# Mosfet_Driver.net
KiCad netlist of a schematic drawn in Altium Designer
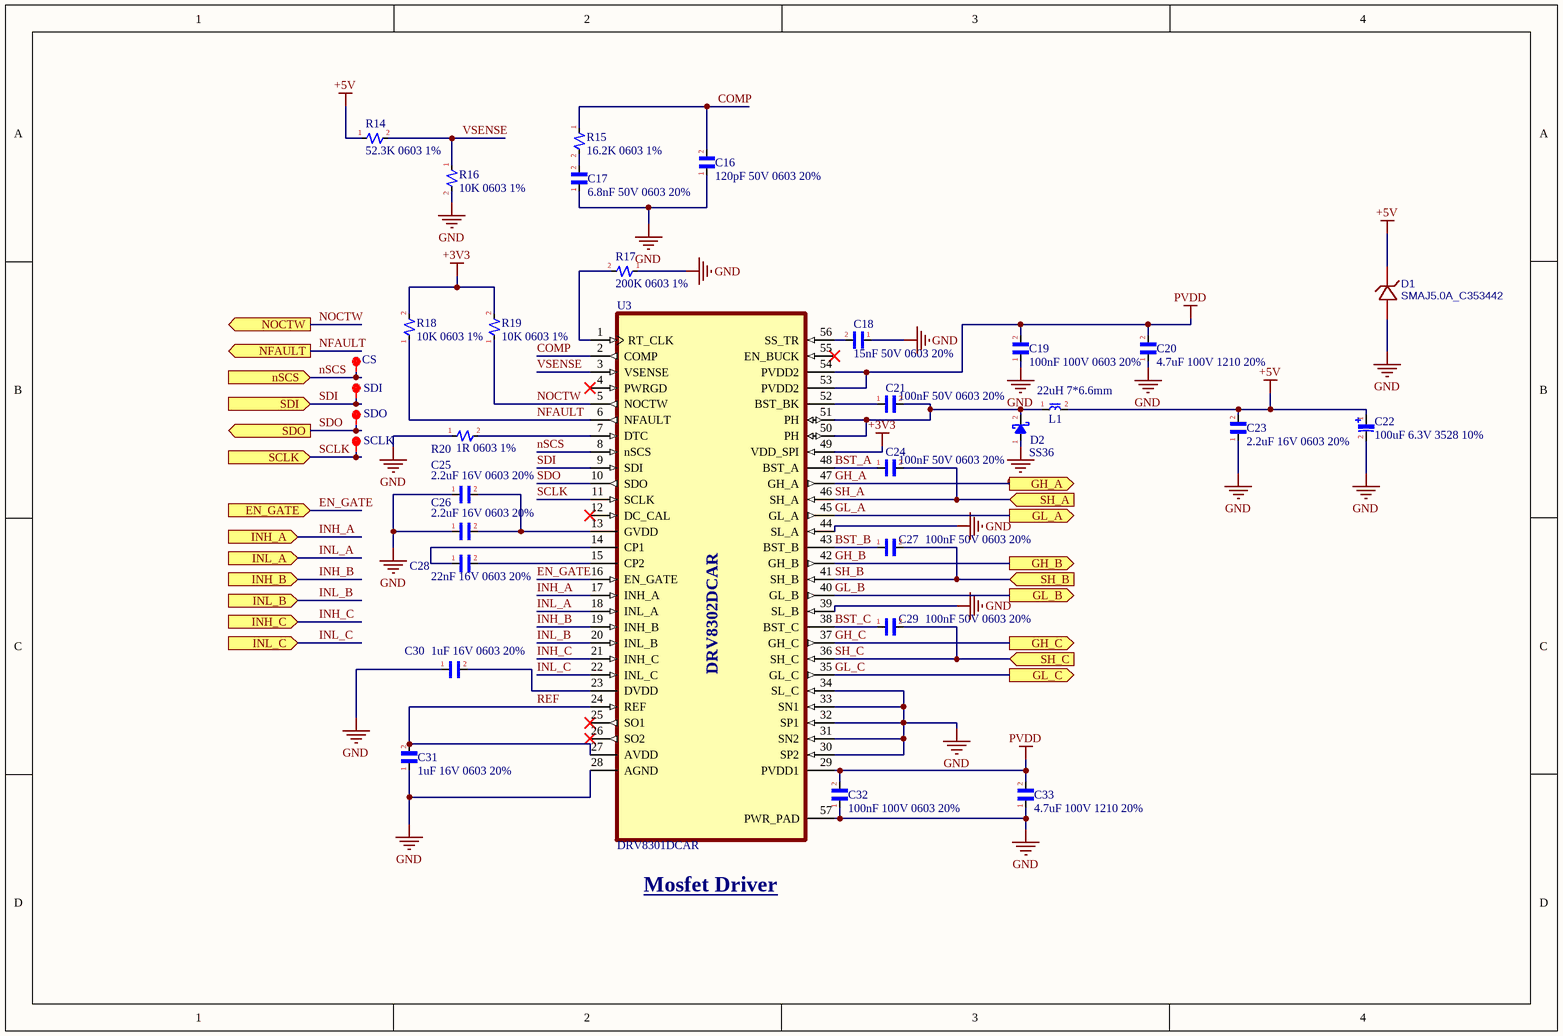
[diagram p0: Mosfet_Driver.SchDoc]

(export (version "E")
  (design (tool "Eeschema 10.0.6"))
  (components
    (comp (ref "C16")
      (value "120pF 50V 0603 20%")
      (footprint "C_0603")
      (description "CAP  0603 20%")
      (libsource (lib "Walton_EED") (part "Capacitor{gt}{gt} Non-Polar"))
    )
    (comp (ref "C17")
      (value "6.8nF 50V 0603 20%")
      (footprint "C_0603")
      (description "CAP  0603 20%")
      (libsource (lib "Walton_EED") (part "Capacitor{gt}{gt} Non-Polar"))
    )
    (comp (ref "C18")
      (value "15nF 50V 0603 20%")
      (footprint "C_0603")
      (description "CAP  0603 20%")
      (libsource (lib "") (part "Capacitor{gt}{gt} Non-Polar_2"))
    )
    (comp (ref "C19")
      (value "100nF 100V 0603 20%")
      (footprint "C_0603")
      (description "CAP  0603 20%")
      (libsource (lib "Walton_EED") (part "Capacitor{gt}{gt} Non-Polar"))
    )
    (comp (ref "C20")
      (value "4.7uF 100V 1210 20%")
      (footprint "C_1210")
      (description "CAP  0603 20%")
      (libsource (lib "Walton_EED") (part "Capacitor{gt}{gt} Non-Polar"))
    )
    (comp (ref "C21")
      (value "100nF 50V 0603 20%")
      (footprint "C_0603")
      (description "CAP  0603 20%")
      (libsource (lib "") (part "Capacitor{gt}{gt} Non-Polar_1"))
    )
    (comp (ref "C22")
      (value "100uF 6.3V 3528 10%")
      (footprint "CAPPC3528X210N")
      (libsource (lib "Walton_EED_13_05_2024") (part "Capacitor{gt}{gt} Polar"))
    )
    (comp (ref "C23")
      (value "2.2uF 16V 0603 20%")
      (footprint "C_0603")
      (description "CAP  0603 20%")
      (libsource (lib "Walton_EED") (part "Capacitor{gt}{gt} Non-Polar"))
    )
    (comp (ref "C24")
      (value "100nF 50V 0603 20%")
      (footprint "C_0603")
      (description "CAP  0603 20%")
      (libsource (lib "") (part "Capacitor{gt}{gt} Non-Polar_1"))
    )
    (comp (ref "C25")
      (value "2.2uF 16V 0603 20%")
      (footprint "C_0603")
      (description "CAP  0603 20%")
      (libsource (lib "") (part "Capacitor{gt}{gt} Non-Polar_1"))
    )
    (comp (ref "C26")
      (value "2.2uF 16V 0603 20%")
      (footprint "C_0603")
      (description "CAP  0603 20%")
      (libsource (lib "") (part "Capacitor{gt}{gt} Non-Polar_1"))
    )
    (comp (ref "C27")
      (value "100nF 50V 0603 20%")
      (footprint "C_0603")
      (description "CAP  0603 20%")
      (libsource (lib "") (part "Capacitor{gt}{gt} Non-Polar_1"))
    )
    (comp (ref "C28")
      (value "22nF 16V 0603 20%")
      (footprint "C_0603")
      (description "CAP  0603 20%")
      (libsource (lib "") (part "Capacitor{gt}{gt} Non-Polar_1"))
    )
    (comp (ref "C29")
      (value "100nF 50V 0603 20%")
      (footprint "C_0603")
      (description "CAP  0603 20%")
      (libsource (lib "") (part "Capacitor{gt}{gt} Non-Polar_1"))
    )
    (comp (ref "C30")
      (value "1uF 16V 0603 20%")
      (footprint "C_0603")
      (description "CAP  0603 20%")
      (libsource (lib "") (part "Capacitor{gt}{gt} Non-Polar_1"))
    )
    (comp (ref "C31")
      (value "1uF 16V 0603 20%")
      (footprint "C_0603")
      (description "CAP  0603 20%")
      (libsource (lib "Walton_EED") (part "Capacitor{gt}{gt} Non-Polar"))
    )
    (comp (ref "C32")
      (value "100nF 100V 0603 20%")
      (footprint "C_0603")
      (description "CAP  0603 20%")
      (libsource (lib "Walton_EED") (part "Capacitor{gt}{gt} Non-Polar"))
    )
    (comp (ref "C33")
      (value "4.7uF 100V 1210 20%")
      (footprint "C_1210")
      (description "CAP  0603 20%")
      (libsource (lib "Walton_EED") (part "Capacitor{gt}{gt} Non-Polar"))
    )
    (comp (ref "D1")
      (value "SMAJ5.0A_C353442")
      (footprint "SMAJ5.0A")
      (fields
        (field (name "BOM_SUPPLIER PART") "C353442")
        (field (name "BOM_MANUFACTURER PART") "SMAJ5.0A")
        (field (name "CONTRIBUTOR") "LCSC")
      )
      (libsource (lib "altium-import") (part "root_3_SMAJ5.0A_C353442_"))
    )
    (comp (ref "D2")
      (value "SS36")
      (footprint "SS54")
      (libsource (lib "Walton_EED_13_05_2024") (part "Diode{gt}{gt}SCHOTTKEY"))
    )
    (comp (ref "L1")
      (value "22uH 7*6.6mm")
      (footprint "Inductor_SMD_7*6.6mm_22uH")
      (libsource (lib "Walton_EED_13_05_2024") (part "Inductor{gt}{gt} General Purpose"))
    )
    (comp (ref "R14")
      (value "52.3K 0603 1%")
      (footprint "R_0603")
      (description "RES 0603 20%")
      (libsource (lib "Walton_EED") (part "Resistor{gt}{gt} General Purpose"))
    )
    (comp (ref "R15")
      (value "16.2K 0603 1%")
      (footprint "R_0603")
      (description "RES 0603 20%")
      (libsource (lib "Walton_EED") (part "Resistor{gt}{gt} General Purpose"))
    )
    (comp (ref "R16")
      (value "10K 0603 1%")
      (footprint "R_0603")
      (description "RES 0603 20%")
      (libsource (lib "Walton_EED") (part "Resistor{gt}{gt} General Purpose"))
    )
    (comp (ref "R17")
      (value "200K 0603 1%")
      (footprint "R_0603")
      (description "RES 0603 20%")
      (libsource (lib "Walton_EED") (part "Resistor{gt}{gt} General Purpose"))
    )
    (comp (ref "R18")
      (value "10K 0603 1%")
      (footprint "R_0603")
      (description "RES 0603 20%")
      (libsource (lib "Walton_EED") (part "Resistor{gt}{gt} General Purpose"))
    )
    (comp (ref "R19")
      (value "10K 0603 1%")
      (footprint "R_0603")
      (description "RES 0603 20%")
      (libsource (lib "Walton_EED") (part "Resistor{gt}{gt} General Purpose"))
    )
    (comp (ref "R20")
      (value "1R 0603 1%")
      (footprint "R_0603")
      (description "RES 0603 20%")
      (libsource (lib "Walton_EED") (part "Resistor{gt}{gt} General Purpose"))
    )
    (comp (ref "TP45") (value "CS") (footprint "TP_1mm_SMD") (libsource (lib "*") (part "Test point TP")))
    (comp (ref "TP46") (value "SDI") (footprint "TP_1mm_SMD") (libsource (lib "*") (part "Test point TP")))
    (comp (ref "TP47") (value "SDO") (footprint "TP_1mm_SMD") (libsource (lib "*") (part "Test point TP")))
    (comp (ref "TP48") (value "SCLK") (footprint "TP_1mm_SMD") (libsource (lib "*") (part "Test point TP")))
    (comp (ref "U3")
      (value "DRV8301DCAR")
      (footprint "TSSOP-56_3")
      (description "Motor Driver Power MOSFET Parallel 56-HTSSOP")
      (fields (field (name "MF") "Texas Instruments") (field (name "MP") "DRV8302DCAR"))
      (libsource (lib "Walton_EED_13_05_2024") (part "DRV8301DCAR"))
    )
  )
  (nets
    (net (code "1") (name "+3V3") (class "Default")
      (node (ref "R18") (pin "2") (pinfunction "2_2") (pintype "passive"))
      (node (ref "R19") (pin "2") (pinfunction "2_2") (pintype "passive"))
      (node (ref "U3") (pin "49") (pinfunction "VDD_SPI_49") (pintype "input"))
    )
    (net (code "2") (name "+5V") (class "Default")
      (node (ref "C22") (pin "1") (pinfunction "1_1") (pintype "passive"))
      (node (ref "C23") (pin "2") (pinfunction "2_2") (pintype "passive"))
      (node (ref "D1") (pin "1") (pinfunction "C_1") (pintype "passive"))
      (node (ref "L1") (pin "2") (pinfunction "2_2") (pintype "passive"))
      (node (ref "R14") (pin "1") (pinfunction "1_1") (pintype "passive"))
    )
    (net (code "3") (name "/BST_A") (class "Default")
      (node (ref "C24") (pin "1") (pinfunction "1_1") (pintype "passive"))
      (node (ref "U3") (pin "48") (pinfunction "BST_A_48") (pintype "power_in"))
    )
    (net (code "4") (name "/BST_B") (class "Default")
      (node (ref "C27") (pin "1") (pinfunction "1_1") (pintype "passive"))
      (node (ref "U3") (pin "43") (pinfunction "BST_B_43") (pintype "power_in"))
    )
    (net (code "5") (name "/BST_C") (class "Default")
      (node (ref "C29") (pin "1") (pinfunction "1_1") (pintype "passive"))
      (node (ref "U3") (pin "38") (pinfunction "BST_C_38") (pintype "power_in"))
    )
    (net (code "6") (name "/COMP") (class "Default")
      (node (ref "C16") (pin "2") (pinfunction "2_2") (pintype "passive"))
      (node (ref "R15") (pin "1") (pinfunction "1_1") (pintype "passive"))
      (node (ref "U3") (pin "2") (pinfunction "COMP_2") (pintype "output"))
    )
    (net (code "7") (name "/EN_GATE") (class "Default")
      (node (ref "U3") (pin "16") (pinfunction "EN_GATE_16") (pintype "input"))
    )
    (net (code "8") (name "/GH_A") (class "Default")
      (node (ref "U3") (pin "47") (pinfunction "GH_A_47") (pintype "output"))
    )
    (net (code "9") (name "/GH_B") (class "Default")
      (node (ref "U3") (pin "42") (pinfunction "GH_B_42") (pintype "output"))
    )
    (net (code "10") (name "/GH_C") (class "Default")
      (node (ref "U3") (pin "37") (pinfunction "GH_C_37") (pintype "output"))
    )
    (net (code "11") (name "/GL_A") (class "Default")
      (node (ref "U3") (pin "45") (pinfunction "GL_A_45") (pintype "output"))
    )
    (net (code "12") (name "/GL_B") (class "Default")
      (node (ref "U3") (pin "40") (pinfunction "GL_B_40") (pintype "output"))
    )
    (net (code "13") (name "/GL_C") (class "Default")
      (node (ref "U3") (pin "35") (pinfunction "GL_C_35") (pintype "output"))
    )
    (net (code "14") (name "/INH_A") (class "Default")
      (node (ref "U3") (pin "17") (pinfunction "INH_A_17") (pintype "input"))
    )
    (net (code "15") (name "/INH_B") (class "Default")
      (node (ref "U3") (pin "19") (pinfunction "INH_B_19") (pintype "input"))
    )
    (net (code "16") (name "/INH_C") (class "Default")
      (node (ref "U3") (pin "21") (pinfunction "INH_C_21") (pintype "input"))
    )
    (net (code "17") (name "/INL_A") (class "Default")
      (node (ref "U3") (pin "18") (pinfunction "INL_A_18") (pintype "input"))
    )
    (net (code "18") (name "/INL_B") (class "Default")
      (node (ref "U3") (pin "20") (pinfunction "INL_B_20") (pintype "input"))
    )
    (net (code "19") (name "/INL_C") (class "Default")
      (node (ref "U3") (pin "22") (pinfunction "INL_C_22") (pintype "input"))
    )
    (net (code "20") (name "/NFAULT") (class "Default")
      (node (ref "R18") (pin "1") (pinfunction "1_1") (pintype "passive"))
      (node (ref "U3") (pin "6") (pinfunction "NFAULT_6") (pintype "output"))
    )
    (net (code "21") (name "/NOCTW") (class "Default")
      (node (ref "R19") (pin "1") (pinfunction "1_1") (pintype "passive"))
      (node (ref "U3") (pin "5") (pinfunction "NOCTW_5") (pintype "output"))
    )
    (net (code "22") (name "/REF") (class "Default")
      (node (ref "C31") (pin "2") (pinfunction "2_2") (pintype "passive"))
      (node (ref "U3") (pin "24") (pinfunction "REF_24") (pintype "input"))
      (node (ref "U3") (pin "27") (pinfunction "AVDD_27") (pintype "power_in"))
    )
    (net (code "23") (name "/SCLK") (class "Default")
      (node (ref "TP48") (pin "1") (pinfunction "1_1") (pintype "passive"))
      (node (ref "U3") (pin "11") (pinfunction "SCLK_11") (pintype "input"))
    )
    (net (code "24") (name "/SDI") (class "Default")
      (node (ref "TP46") (pin "1") (pinfunction "1_1") (pintype "passive"))
      (node (ref "U3") (pin "9") (pinfunction "SDI_9") (pintype "input"))
    )
    (net (code "25") (name "/SDO") (class "Default")
      (node (ref "TP47") (pin "1") (pinfunction "1_1") (pintype "passive"))
      (node (ref "U3") (pin "10") (pinfunction "SDO_10") (pintype "output"))
    )
    (net (code "26") (name "/SH_A") (class "Default")
      (node (ref "C24") (pin "2") (pinfunction "2_2") (pintype "passive"))
      (node (ref "U3") (pin "46") (pinfunction "SH_A_46") (pintype "input"))
    )
    (net (code "27") (name "/SH_B") (class "Default")
      (node (ref "C27") (pin "2") (pinfunction "2_2") (pintype "passive"))
      (node (ref "U3") (pin "41") (pinfunction "SH_B_41") (pintype "input"))
    )
    (net (code "28") (name "/SH_C") (class "Default")
      (node (ref "C29") (pin "2") (pinfunction "2_2") (pintype "passive"))
      (node (ref "U3") (pin "36") (pinfunction "SH_C_36") (pintype "input"))
    )
    (net (code "29") (name "/VSENSE") (class "Default")
      (node (ref "R14") (pin "2") (pinfunction "2_2") (pintype "passive"))
      (node (ref "R16") (pin "1") (pinfunction "1_1") (pintype "passive"))
      (node (ref "U3") (pin "3") (pinfunction "VSENSE_3") (pintype "input"))
    )
    (net (code "30") (name "/nSCS") (class "Default")
      (node (ref "TP45") (pin "1") (pinfunction "1_1") (pintype "passive"))
      (node (ref "U3") (pin "8") (pinfunction "nSCS_8") (pintype "input"))
    )
    (net (code "31") (name "GND") (class "Default")
      (node (ref "C16") (pin "1") (pinfunction "1_1") (pintype "passive"))
      (node (ref "C17") (pin "1") (pinfunction "1_1") (pintype "passive"))
      (node (ref "C18") (pin "1") (pinfunction "1_1") (pintype "passive"))
      (node (ref "C19") (pin "1") (pinfunction "1_1") (pintype "passive"))
      (node (ref "C20") (pin "1") (pinfunction "1_1") (pintype "passive"))
      (node (ref "C22") (pin "2") (pinfunction "2_2") (pintype "passive"))
      (node (ref "C23") (pin "1") (pinfunction "1_1") (pintype "passive"))
      (node (ref "C25") (pin "1") (pinfunction "1_1") (pintype "passive"))
      (node (ref "C26") (pin "1") (pinfunction "1_1") (pintype "passive"))
      (node (ref "C30") (pin "1") (pinfunction "1_1") (pintype "passive"))
      (node (ref "C31") (pin "1") (pinfunction "1_1") (pintype "passive"))
      (node (ref "C32") (pin "1") (pinfunction "1_1") (pintype "passive"))
      (node (ref "C33") (pin "1") (pinfunction "1_1") (pintype "passive"))
      (node (ref "D1") (pin "2") (pinfunction "A_2") (pintype "passive"))
      (node (ref "D2") (pin "1") (pinfunction "A1_1") (pintype "passive"))
      (node (ref "R16") (pin "2") (pinfunction "2_2") (pintype "passive"))
      (node (ref "R17") (pin "1") (pinfunction "1_1") (pintype "passive"))
      (node (ref "R20") (pin "1") (pinfunction "1_1") (pintype "passive"))
      (node (ref "U3") (pin "28") (pinfunction "AGND_28") (pintype "power_in"))
      (node (ref "U3") (pin "30") (pinfunction "SP2_30") (pintype "input"))
      (node (ref "U3") (pin "31") (pinfunction "SN2_31") (pintype "input"))
      (node (ref "U3") (pin "32") (pinfunction "SP1_32") (pintype "input"))
      (node (ref "U3") (pin "33") (pinfunction "SN1_33") (pintype "input"))
      (node (ref "U3") (pin "34") (pinfunction "SL_C_34") (pintype "input"))
      (node (ref "U3") (pin "39") (pinfunction "SL_B_39") (pintype "input"))
      (node (ref "U3") (pin "44") (pinfunction "SL_A_44") (pintype "input"))
      (node (ref "U3") (pin "57") (pinfunction "PWR_PAD_57") (pintype "power_in"))
    )
    (net (code "32") (name "Net-(C17-Pad2)") (class "Default")
      (node (ref "C17") (pin "2") (pinfunction "2_2") (pintype "passive"))
      (node (ref "R15") (pin "2") (pinfunction "2_2") (pintype "passive"))
    )
    (net (code "33") (name "Net-(D2-K)") (class "Default")
      (node (ref "C21") (pin "2") (pinfunction "2_2") (pintype "passive"))
      (node (ref "D2") (pin "2") (pinfunction "K_2") (pintype "passive"))
      (node (ref "L1") (pin "1") (pinfunction "1_1") (pintype "passive"))
      (node (ref "U3") (pin "50") (pinfunction "PH_50") (pintype "bidirectional"))
      (node (ref "U3") (pin "51") (pinfunction "PH_51") (pintype "bidirectional"))
    )
    (net (code "34") (name "Net-(U3-BST_BK)") (class "Default")
      (node (ref "C21") (pin "1") (pinfunction "1_1") (pintype "passive"))
      (node (ref "U3") (pin "52") (pinfunction "BST_BK_52") (pintype "power_in"))
    )
    (net (code "35") (name "Net-(U3-CP1)") (class "Default")
      (node (ref "C28") (pin "1") (pinfunction "1_1") (pintype "passive"))
      (node (ref "U3") (pin "14") (pinfunction "CP1_14") (pintype "power_in"))
    )
    (net (code "36") (name "Net-(U3-CP2)") (class "Default")
      (node (ref "C28") (pin "2") (pinfunction "2_2") (pintype "passive"))
      (node (ref "U3") (pin "15") (pinfunction "CP2_15") (pintype "power_in"))
    )
    (net (code "37") (name "Net-(U3-DTC)") (class "Default")
      (node (ref "R20") (pin "2") (pinfunction "2_2") (pintype "passive"))
      (node (ref "U3") (pin "7") (pinfunction "DTC_7") (pintype "input"))
    )
    (net (code "38") (name "Net-(U3-DVDD)") (class "Default")
      (node (ref "C30") (pin "2") (pinfunction "2_2") (pintype "passive"))
      (node (ref "U3") (pin "23") (pinfunction "DVDD_23") (pintype "power_in"))
    )
    (net (code "39") (name "Net-(U3-GVDD)") (class "Default")
      (node (ref "C25") (pin "2") (pinfunction "2_2") (pintype "passive"))
      (node (ref "C26") (pin "2") (pinfunction "2_2") (pintype "passive"))
      (node (ref "U3") (pin "13") (pinfunction "GVDD_13") (pintype "power_in"))
    )
    (net (code "40") (name "Net-(U3-RT_CLK)") (class "Default")
      (node (ref "R17") (pin "2") (pinfunction "2_2") (pintype "passive"))
      (node (ref "U3") (pin "1") (pinfunction "RT_CLK_1") (pintype "input"))
    )
    (net (code "41") (name "Net-(U3-SS_TR)") (class "Default")
      (node (ref "C18") (pin "2") (pinfunction "2_2") (pintype "passive"))
      (node (ref "U3") (pin "56") (pinfunction "SS_TR_56") (pintype "input"))
    )
    (net (code "42") (name "PVDD") (class "Default")
      (node (ref "C19") (pin "2") (pinfunction "2_2") (pintype "passive"))
      (node (ref "C20") (pin "2") (pinfunction "2_2") (pintype "passive"))
      (node (ref "C32") (pin "2") (pinfunction "2_2") (pintype "passive"))
      (node (ref "C33") (pin "2") (pinfunction "2_2") (pintype "passive"))
      (node (ref "U3") (pin "29") (pinfunction "PVDD1_29") (pintype "power_in"))
      (node (ref "U3") (pin "53") (pinfunction "PVDD2_53") (pintype "power_in"))
      (node (ref "U3") (pin "54") (pinfunction "PVDD2_54") (pintype "power_in"))
    )
    (net (code "43") (name "unconnected-(U3-DC_CAL-Pad12)") (class "Default")
      (node (ref "U3") (pin "12") (pinfunction "DC_CAL_12") (pintype "input+no_connect"))
    )
    (net (code "44") (name "unconnected-(U3-EN_BUCK-Pad55)") (class "Default")
      (node (ref "U3") (pin "55") (pinfunction "EN_BUCK_55") (pintype "input+no_connect"))
    )
    (net (code "45") (name "unconnected-(U3-PWRGD-Pad4)") (class "Default")
      (node (ref "U3") (pin "4") (pinfunction "PWRGD_4") (pintype "input+no_connect"))
    )
    (net (code "46") (name "unconnected-(U3-SO1-Pad25)") (class "Default")
      (node (ref "U3") (pin "25") (pinfunction "SO1_25") (pintype "output+no_connect"))
    )
    (net (code "47") (name "unconnected-(U3-SO2-Pad26)") (class "Default")
      (node (ref "U3") (pin "26") (pinfunction "SO2_26") (pintype "output+no_connect"))
    )
  )
)
